# motherboard.net
KiCad netlist of a schematic drawn in EAGLE
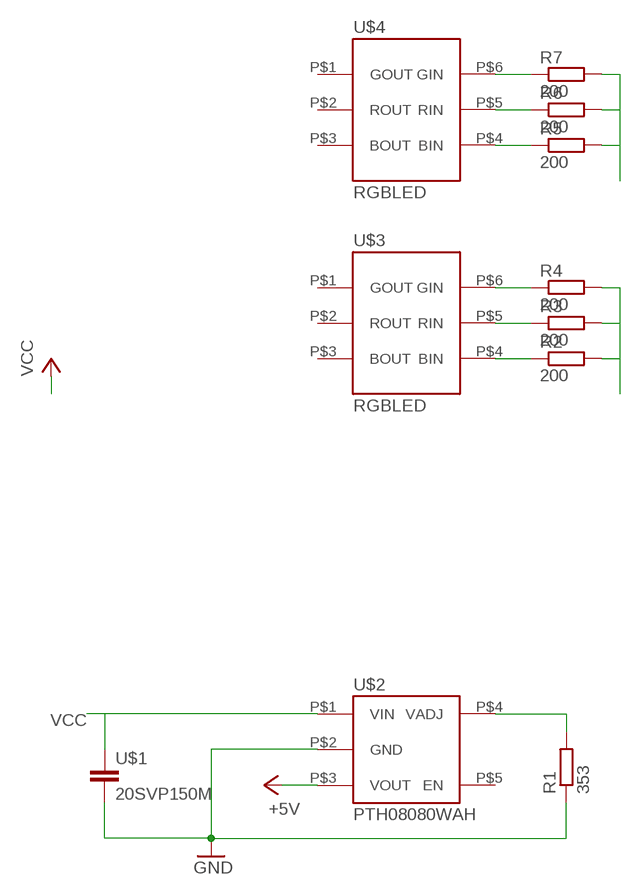
[diagram p0: schematic, sheet 1]

(export (version "E")
  (design (tool "Eeschema 10.0.6"))
  (components
    (comp (ref "R1")
      (value "353")
      (footprint "eagle-import:R0805")
      (libsource (lib "eagle-import") (part "R-EU_R0805"))
    )
    (comp (ref "R2")
      (value "200")
      (footprint "eagle-import:R0805")
      (libsource (lib "eagle-import") (part "R-EU_R0805"))
    )
    (comp (ref "R3")
      (value "200")
      (footprint "eagle-import:R0805")
      (libsource (lib "eagle-import") (part "R-EU_R0805"))
    )
    (comp (ref "R4")
      (value "200")
      (footprint "eagle-import:R0805")
      (libsource (lib "eagle-import") (part "R-EU_R0805"))
    )
    (comp (ref "R5")
      (value "200")
      (footprint "eagle-import:R0805")
      (libsource (lib "eagle-import") (part "R-EU_R0805"))
    )
    (comp (ref "R6")
      (value "200")
      (footprint "eagle-import:R0805")
      (libsource (lib "eagle-import") (part "R-EU_R0805"))
    )
    (comp (ref "R7")
      (value "200")
      (footprint "eagle-import:R0805")
      (libsource (lib "eagle-import") (part "R-EU_R0805"))
    )
    (comp (ref "U$1")
      (value "20SVP150M")
      (footprint "eagle-import:20SVP150M")
      (libsource (lib "eagle-import") (part "20SVP150M"))
    )
    (comp (ref "U$2")
      (value "PTH08080WAH")
      (footprint "eagle-import:PTH08080WAH")
      (libsource (lib "eagle-import") (part "PTH08080WAH"))
    )
    (comp (ref "U$3")
      (value "RGBLED")
      (footprint "eagle-import:RGBLED")
      (libsource (lib "eagle-import") (part "RGBLED"))
    )
    (comp (ref "U$4")
      (value "RGBLED")
      (footprint "eagle-import:RGBLED")
      (libsource (lib "eagle-import") (part "RGBLED"))
    )
  )
  (nets
    (net (code "1") (name "+5V") (class "Default")
      (node (ref "U$2") (pin "P$3") (pinfunction "VOUT_P$3") (pintype "output"))
    )
    (net (code "2") (name "GND") (class "Default")
      (node (ref "R1") (pin "1") (pinfunction "1_1") (pintype "passive"))
      (node (ref "U$1") (pin "P$1") (pinfunction "2_P$1") (pintype "passive"))
      (node (ref "U$2") (pin "P$2") (pinfunction "GND_P$2") (pintype "power_in"))
    )
    (net (code "3") (name "Net-(R2-Pad2)") (class "Default")
      (node (ref "R2") (pin "2") (pinfunction "2_2") (pintype "passive"))
      (node (ref "R3") (pin "2") (pinfunction "2_2") (pintype "passive"))
      (node (ref "R4") (pin "2") (pinfunction "2_2") (pintype "passive"))
    )
    (net (code "4") (name "Net-(R5-Pad2)") (class "Default")
      (node (ref "R5") (pin "2") (pinfunction "2_2") (pintype "passive"))
      (node (ref "R6") (pin "2") (pinfunction "2_2") (pintype "passive"))
      (node (ref "R7") (pin "2") (pinfunction "2_2") (pintype "passive"))
    )
    (net (code "5") (name "Net-(U$2-VADJ)") (class "Default")
      (node (ref "R1") (pin "2") (pinfunction "2_2") (pintype "passive"))
      (node (ref "U$2") (pin "P$4") (pinfunction "VADJ_P$4") (pintype "input"))
    )
    (net (code "6") (name "Net-(U$3-BIN)") (class "Default")
      (node (ref "R2") (pin "1") (pinfunction "1_1") (pintype "passive"))
      (node (ref "U$3") (pin "P$4") (pinfunction "BIN_P$4") (pintype "bidirectional"))
    )
    (net (code "7") (name "Net-(U$3-GIN)") (class "Default")
      (node (ref "R4") (pin "1") (pinfunction "1_1") (pintype "passive"))
      (node (ref "U$3") (pin "P$6") (pinfunction "GIN_P$6") (pintype "bidirectional"))
    )
    (net (code "8") (name "Net-(U$3-RIN)") (class "Default")
      (node (ref "R3") (pin "1") (pinfunction "1_1") (pintype "passive"))
      (node (ref "U$3") (pin "P$5") (pinfunction "RIN_P$5") (pintype "bidirectional"))
    )
    (net (code "9") (name "Net-(U$4-BIN)") (class "Default")
      (node (ref "R5") (pin "1") (pinfunction "1_1") (pintype "passive"))
      (node (ref "U$4") (pin "P$4") (pinfunction "BIN_P$4") (pintype "bidirectional"))
    )
    (net (code "10") (name "Net-(U$4-GIN)") (class "Default")
      (node (ref "R7") (pin "1") (pinfunction "1_1") (pintype "passive"))
      (node (ref "U$4") (pin "P$6") (pinfunction "GIN_P$6") (pintype "bidirectional"))
    )
    (net (code "11") (name "Net-(U$4-RIN)") (class "Default")
      (node (ref "R6") (pin "1") (pinfunction "1_1") (pintype "passive"))
      (node (ref "U$4") (pin "P$5") (pinfunction "RIN_P$5") (pintype "bidirectional"))
    )
    (net (code "12") (name "VCC") (class "Default")
      (node (ref "U$1") (pin "P$2") (pinfunction "1_P$2") (pintype "passive"))
      (node (ref "U$2") (pin "P$1") (pinfunction "VIN_P$1") (pintype "power_in"))
    )
    (net (code "13") (name "unconnected-(U$2-EN-PadP$5)") (class "Default")
      (node (ref "U$2") (pin "P$5") (pinfunction "EN_P$5") (pintype "input"))
    )
    (net (code "14") (name "unconnected-(U$3-BOUT-PadP$3)") (class "Default")
      (node (ref "U$3") (pin "P$3") (pinfunction "BOUT_P$3") (pintype "bidirectional"))
    )
    (net (code "15") (name "unconnected-(U$3-GOUT-PadP$1)") (class "Default")
      (node (ref "U$3") (pin "P$1") (pinfunction "GOUT_P$1") (pintype "bidirectional"))
    )
    (net (code "16") (name "unconnected-(U$3-ROUT-PadP$2)") (class "Default")
      (node (ref "U$3") (pin "P$2") (pinfunction "ROUT_P$2") (pintype "bidirectional"))
    )
    (net (code "17") (name "unconnected-(U$4-BOUT-PadP$3)") (class "Default")
      (node (ref "U$4") (pin "P$3") (pinfunction "BOUT_P$3") (pintype "bidirectional"))
    )
    (net (code "18") (name "unconnected-(U$4-GOUT-PadP$1)") (class "Default")
      (node (ref "U$4") (pin "P$1") (pinfunction "GOUT_P$1") (pintype "bidirectional"))
    )
    (net (code "19") (name "unconnected-(U$4-ROUT-PadP$2)") (class "Default")
      (node (ref "U$4") (pin "P$2") (pinfunction "ROUT_P$2") (pintype "bidirectional"))
    )
  )
)
